# EEG-RM_040218P03.net
KiCad netlist of a schematic drawn in EAGLE
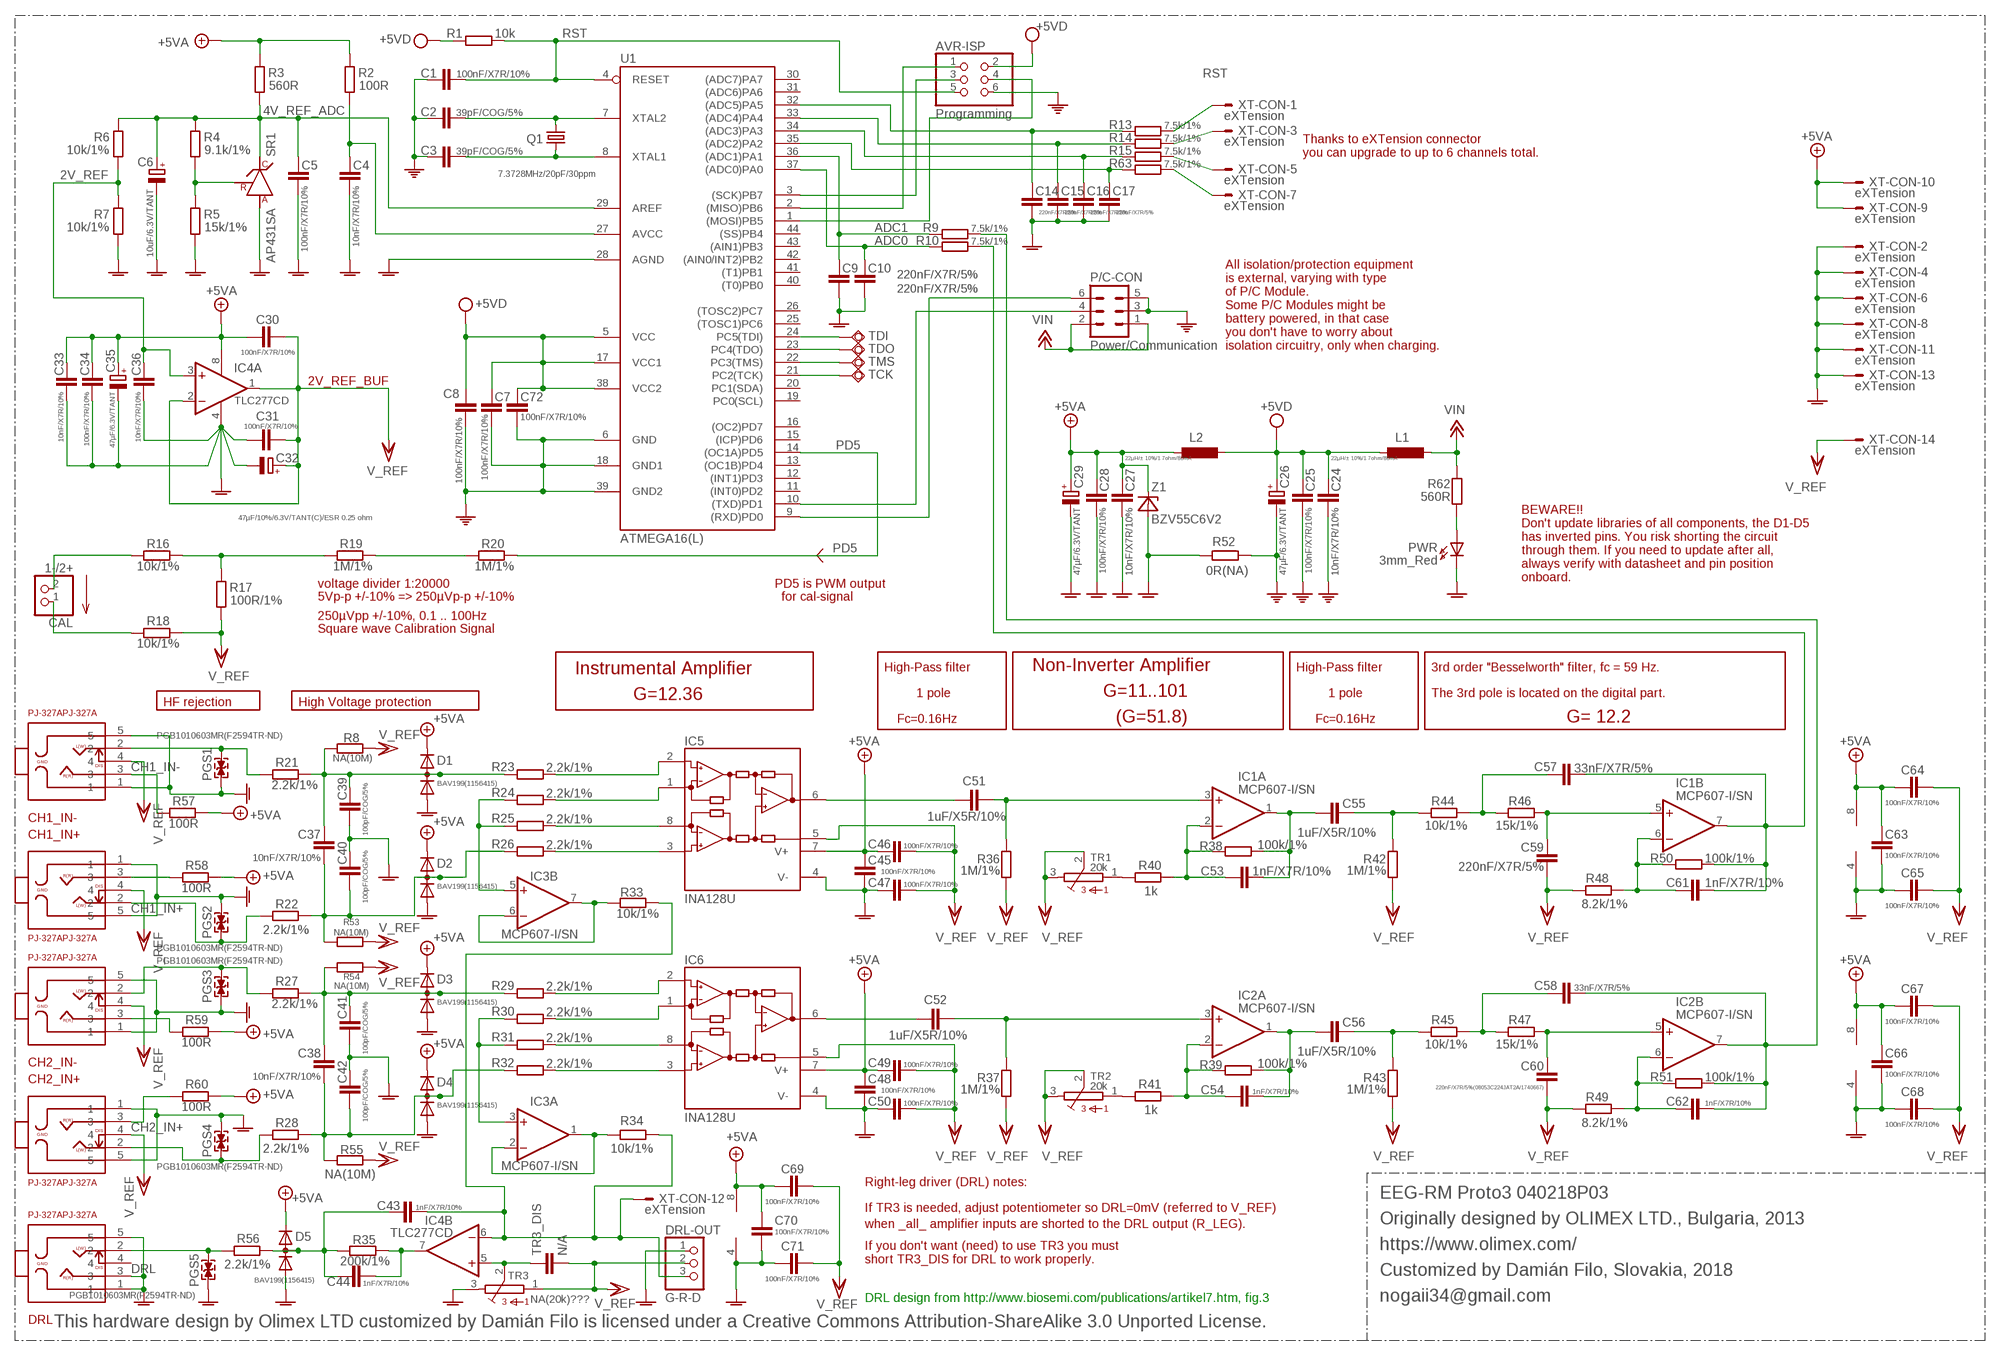
[diagram p0: schematic, sheet 1]

(export (version "E")
  (design (tool "Eeschema 10.0.6"))
  (components
    (comp (ref "AVR-ISP")
      (value "Programming")
      (footprint "eagle-import:2X03")
      (libsource (lib "eagle-import") (part "PINHD-2X3"))
    )
    (comp (ref "C1")
      (value "100nF/X7R/10%")
      (footprint "eagle-import:C0603")
      (libsource (lib "eagle-import") (part "C-EUC0603"))
    )
    (comp (ref "C2")
      (value "39pF/COG/5%")
      (footprint "eagle-import:C0603")
      (libsource (lib "eagle-import") (part "C-EUC0603"))
    )
    (comp (ref "C3")
      (value "39pF/COG/5%")
      (footprint "eagle-import:C0603")
      (libsource (lib "eagle-import") (part "C-EUC0603"))
    )
    (comp (ref "C4")
      (value "10nF/X7R/10%")
      (footprint "eagle-import:C0603")
      (libsource (lib "eagle-import") (part "C-EUC0603"))
    )
    (comp (ref "C5")
      (value "100nF/X7R/10%")
      (footprint "eagle-import:C0603")
      (libsource (lib "eagle-import") (part "C-EUC0603"))
    )
    (comp (ref "C6")
      (value "10uF/6.3V/TANT")
      (footprint "eagle-import:CT3216")
      (libsource (lib "eagle-import") (part "CPOL-EUCT3216"))
    )
    (comp (ref "C7")
      (value "100nF/X7R/10%")
      (footprint "eagle-import:C0603")
      (libsource (lib "eagle-import") (part "C-EUC0603"))
    )
    (comp (ref "C8")
      (value "100nF/X7R/10%")
      (footprint "eagle-import:C0603")
      (libsource (lib "eagle-import") (part "C-EUC0603"))
    )
    (comp (ref "C9")
      (value "220nF/X7R/5%")
      (footprint "eagle-import:C0603")
      (libsource (lib "eagle-import") (part "C-EUC0603"))
    )
    (comp (ref "C10")
      (value "220nF/X7R/5%")
      (footprint "eagle-import:C0603")
      (libsource (lib "eagle-import") (part "C-EUC0603"))
    )
    (comp (ref "C14")
      (value "220nF/X7R/5%")
      (footprint "eagle-import:C0603")
      (libsource (lib "eagle-import") (part "C-EUC0603"))
    )
    (comp (ref "C15")
      (value "220nF/X7R/5%")
      (footprint "eagle-import:C0603")
      (libsource (lib "eagle-import") (part "C-EUC0603"))
    )
    (comp (ref "C16")
      (value "220nF/X7R/5%")
      (footprint "eagle-import:C0603")
      (libsource (lib "eagle-import") (part "C-EUC0603"))
    )
    (comp (ref "C17")
      (value "220nF/X7R/5%")
      (footprint "eagle-import:C0603")
      (libsource (lib "eagle-import") (part "C-EUC0603"))
    )
    (comp (ref "C24")
      (value "10nF/X7R/10%")
      (footprint "eagle-import:C0603")
      (libsource (lib "eagle-import") (part "C-EUC0603"))
    )
    (comp (ref "C25")
      (value "100nF/X7R/10%")
      (footprint "eagle-import:C0603")
      (libsource (lib "eagle-import") (part "C-EUC0603"))
    )
    (comp (ref "C26")
      (value "47µF/6.3V/TANT")
      (footprint "eagle-import:CT3216")
      (libsource (lib "eagle-import") (part "CPOL-EUCT3216"))
    )
    (comp (ref "C27")
      (value "10nF/X7R/10%")
      (footprint "eagle-import:C0603")
      (libsource (lib "eagle-import") (part "C-EUC0603"))
    )
    (comp (ref "C28")
      (value "100nF/X7R/10%")
      (footprint "eagle-import:C0603")
      (libsource (lib "eagle-import") (part "C-EUC0603"))
    )
    (comp (ref "C29")
      (value "47µF/6.3V/TANT")
      (footprint "eagle-import:CT3216")
      (libsource (lib "eagle-import") (part "CPOL-EUCT3216"))
    )
    (comp (ref "C30")
      (value "100nF/X7R/10%")
      (footprint "eagle-import:C0603")
      (libsource (lib "eagle-import") (part "C-EUC0603"))
    )
    (comp (ref "C31")
      (value "100nF/X7R/10%")
      (footprint "eagle-import:C0603")
      (libsource (lib "eagle-import") (part "C-EUC0603"))
    )
    (comp (ref "C32")
      (value "47µF/10%/6.3V/TANT(C)/ESR 0.25 ohm")
      (footprint "eagle-import:CT3528")
      (libsource (lib "eagle-import") (part "CPOL-EUCT3528"))
    )
    (comp (ref "C33")
      (value "10nF/X7R/10%")
      (footprint "eagle-import:C0603")
      (libsource (lib "eagle-import") (part "C-EUC0603"))
    )
    (comp (ref "C34")
      (value "100nF/X7R/10%")
      (footprint "eagle-import:C0603")
      (libsource (lib "eagle-import") (part "C-EUC0603"))
    )
    (comp (ref "C35")
      (value "47µF/6.3V/TANT")
      (footprint "eagle-import:CT3216")
      (libsource (lib "eagle-import") (part "CPOL-EUCT3216"))
    )
    (comp (ref "C36")
      (value "10nF/X7R/10%")
      (footprint "eagle-import:C0603")
      (libsource (lib "eagle-import") (part "C-EUC0603"))
    )
    (comp (ref "C37")
      (value "10nF/X7R/10%")
      (footprint "eagle-import:C0603")
      (libsource (lib "eagle-import") (part "C-EUC0603"))
    )
    (comp (ref "C38")
      (value "10nF/X7R/10%")
      (footprint "eagle-import:C0603")
      (libsource (lib "eagle-import") (part "C-EUC0603"))
    )
    (comp (ref "C39")
      (value "100pF/COG/5%")
      (footprint "eagle-import:C0603")
      (libsource (lib "eagle-import") (part "C-EUC0603"))
    )
    (comp (ref "C40")
      (value "100pF/COG/5%")
      (footprint "eagle-import:C0603")
      (libsource (lib "eagle-import") (part "C-EUC0603"))
    )
    (comp (ref "C41")
      (value "100pF/COG/5%")
      (footprint "eagle-import:C0603")
      (libsource (lib "eagle-import") (part "C-EUC0603"))
    )
    (comp (ref "C42")
      (value "100pF/COG/5%")
      (footprint "eagle-import:C0603")
      (libsource (lib "eagle-import") (part "C-EUC0603"))
    )
    (comp (ref "C43")
      (value "1nF/X7R/10%")
      (footprint "eagle-import:C0603")
      (libsource (lib "eagle-import") (part "C-EUC0603"))
    )
    (comp (ref "C44")
      (value "1nF/X7R/10%")
      (footprint "eagle-import:C0603")
      (libsource (lib "eagle-import") (part "C-EUC0603"))
    )
    (comp (ref "C45")
      (value "100nF/X7R/10%")
      (footprint "eagle-import:C0603")
      (libsource (lib "eagle-import") (part "C-EUC0603"))
    )
    (comp (ref "C46")
      (value "100nF/X7R/10%")
      (footprint "eagle-import:C0603")
      (libsource (lib "eagle-import") (part "C-EUC0603"))
    )
    (comp (ref "C47")
      (value "100nF/X7R/10%")
      (footprint "eagle-import:C0603")
      (libsource (lib "eagle-import") (part "C-EUC0603"))
    )
    (comp (ref "C48")
      (value "100nF/X7R/10%")
      (footprint "eagle-import:C0603")
      (libsource (lib "eagle-import") (part "C-EUC0603"))
    )
    (comp (ref "C49")
      (value "100nF/X7R/10%")
      (footprint "eagle-import:C0603")
      (libsource (lib "eagle-import") (part "C-EUC0603"))
    )
    (comp (ref "C50")
      (value "100nF/X7R/10%")
      (footprint "eagle-import:C0603")
      (libsource (lib "eagle-import") (part "C-EUC0603"))
    )
    (comp (ref "C51")
      (value "1uF/X5R/10%")
      (footprint "eagle-import:C0603")
      (libsource (lib "eagle-import") (part "C-EUC0603"))
    )
    (comp (ref "C52")
      (value "1uF/X5R/10%")
      (footprint "eagle-import:C0603")
      (libsource (lib "eagle-import") (part "C-EUC0603"))
    )
    (comp (ref "C53")
      (value "1nF/X7R/10%")
      (footprint "eagle-import:C0603")
      (libsource (lib "eagle-import") (part "C-EUC0603"))
    )
    (comp (ref "C54")
      (value "1nF/X7R/10%")
      (footprint "eagle-import:C0603")
      (libsource (lib "eagle-import") (part "C-EUC0603"))
    )
    (comp (ref "C55")
      (value "1uF/X5R/10%")
      (footprint "eagle-import:C0603")
      (libsource (lib "eagle-import") (part "C-EUC0603"))
    )
    (comp (ref "C56")
      (value "1uF/X5R/10%")
      (footprint "eagle-import:C0603")
      (libsource (lib "eagle-import") (part "C-EUC0603"))
    )
    (comp (ref "C57")
      (value "33nF/X7R/5%")
      (footprint "eagle-import:C0603")
      (libsource (lib "eagle-import") (part "C-EUC0603"))
    )
    (comp (ref "C58")
      (value "33nF/X7R/5%")
      (footprint "eagle-import:C0603")
      (libsource (lib "eagle-import") (part "C-EUC0603"))
    )
    (comp (ref "C59")
      (value "220nF/X7R/5%")
      (footprint "eagle-import:C0603")
      (libsource (lib "eagle-import") (part "C-EUC0603"))
    )
    (comp (ref "C60")
      (value "220nF/X7R/5%(08053C224JAT2A/1740667)")
      (footprint "eagle-import:C0603")
      (libsource (lib "eagle-import") (part "C-EUC0603"))
    )
    (comp (ref "C61")
      (value "1nF/X7R/10%")
      (footprint "eagle-import:C0603")
      (libsource (lib "eagle-import") (part "C-EUC0603"))
    )
    (comp (ref "C62")
      (value "1nF/X7R/10%")
      (footprint "eagle-import:C0603")
      (libsource (lib "eagle-import") (part "C-EUC0603"))
    )
    (comp (ref "C63")
      (value "100nF/X7R/10%")
      (footprint "eagle-import:C0603")
      (libsource (lib "eagle-import") (part "C-EUC0603"))
    )
    (comp (ref "C64")
      (value "100nF/X7R/10%")
      (footprint "eagle-import:C0603")
      (libsource (lib "eagle-import") (part "C-EUC0603"))
    )
    (comp (ref "C65")
      (value "100nF/X7R/10%")
      (footprint "eagle-import:C0603")
      (libsource (lib "eagle-import") (part "C-EUC0603"))
    )
    (comp (ref "C66")
      (value "100nF/X7R/10%")
      (footprint "eagle-import:C0603")
      (libsource (lib "eagle-import") (part "C-EUC0603"))
    )
    (comp (ref "C67")
      (value "100nF/X7R/10%")
      (footprint "eagle-import:C0603")
      (libsource (lib "eagle-import") (part "C-EUC0603"))
    )
    (comp (ref "C68")
      (value "100nF/X7R/10%")
      (footprint "eagle-import:C0603")
      (libsource (lib "eagle-import") (part "C-EUC0603"))
    )
    (comp (ref "C69")
      (value "100nF/X7R/10%")
      (footprint "eagle-import:C0603")
      (libsource (lib "eagle-import") (part "C-EUC0603"))
    )
    (comp (ref "C70")
      (value "100nF/X7R/10%")
      (footprint "eagle-import:C0603")
      (libsource (lib "eagle-import") (part "C-EUC0603"))
    )
    (comp (ref "C71")
      (value "100nF/X7R/10%")
      (footprint "eagle-import:C0603")
      (libsource (lib "eagle-import") (part "C-EUC0603"))
    )
    (comp (ref "C72")
      (value "100nF/X7R/10%")
      (footprint "eagle-import:C0603")
      (libsource (lib "eagle-import") (part "C-EUC0603"))
    )
    (comp (ref "CAL")
      (value "1-/2+")
      (footprint "eagle-import:1X02")
      (libsource (lib "eagle-import") (part "PINHD-1X2"))
    )
    (comp (ref "CH1_IN+")
      (value "PJ-327APJ-327A")
      (footprint "eagle-import:PJ-327A")
      (libsource (lib "eagle-import") (part "PJ-327APJ-327A"))
    )
    (comp (ref "CH1_IN-")
      (value "PJ-327APJ-327A")
      (footprint "eagle-import:PJ-327A")
      (libsource (lib "eagle-import") (part "PJ-327APJ-327A"))
    )
    (comp (ref "CH2_IN+")
      (value "PJ-327APJ-327A")
      (footprint "eagle-import:PJ-327A")
      (libsource (lib "eagle-import") (part "PJ-327APJ-327A"))
    )
    (comp (ref "CH2_IN-")
      (value "PJ-327APJ-327A")
      (footprint "eagle-import:PJ-327A")
      (libsource (lib "eagle-import") (part "PJ-327APJ-327A"))
    )
    (comp (ref "D1")
      (value "BAV199(1156415)")
      (footprint "eagle-import:SOT23C")
      (libsource (lib "eagle-import") (part "DIODE_AC-AC__"))
    )
    (comp (ref "D2")
      (value "BAV199(1156415)")
      (footprint "eagle-import:SOT23C")
      (libsource (lib "eagle-import") (part "DIODE_AC-AC__"))
    )
    (comp (ref "D3")
      (value "BAV199(1156415)")
      (footprint "eagle-import:SOT23C")
      (libsource (lib "eagle-import") (part "DIODE_AC-AC__"))
    )
    (comp (ref "D4")
      (value "BAV199(1156415)")
      (footprint "eagle-import:SOT23C")
      (libsource (lib "eagle-import") (part "DIODE_AC-AC__"))
    )
    (comp (ref "D5")
      (value "BAV199(1156415)")
      (footprint "eagle-import:SOT23C")
      (libsource (lib "eagle-import") (part "DIODE_AC-AC__"))
    )
    (comp (ref "DRL")
      (value "PJ-327APJ-327A")
      (footprint "eagle-import:PJ-327A")
      (libsource (lib "eagle-import") (part "PJ-327APJ-327A"))
    )
    (comp (ref "DRL-OUT")
      (value "G-R-D")
      (footprint "eagle-import:1X03")
      (libsource (lib "eagle-import") (part "PINHD-1X3"))
    )
    (comp (ref "IC1")
      (value "MCP607-I/SN")
      (footprint "eagle-import:SO08")
      (libsource (lib "eagle-import") (part "LM358D"))
    )
    (comp (ref "IC2")
      (value "MCP607-I/SN")
      (footprint "eagle-import:SO08")
      (libsource (lib "eagle-import") (part "LM358D"))
    )
    (comp (ref "IC3")
      (value "MCP607-I/SN")
      (footprint "eagle-import:SO08")
      (libsource (lib "eagle-import") (part "LM358D"))
    )
    (comp (ref "IC4")
      (value "TLC277CD")
      (footprint "eagle-import:SO08")
      (libsource (lib "eagle-import") (part "LM358D"))
    )
    (comp (ref "IC5")
      (value "INA128U")
      (footprint "eagle-import:SO08")
      (fields (field (name "MF") "TEXAS INSTRUMENTS"))
      (libsource (lib "eagle-import") (part "INA128U"))
    )
    (comp (ref "IC6")
      (value "INA128U")
      (footprint "eagle-import:SO08")
      (fields (field (name "MF") "TEXAS INSTRUMENTS"))
      (libsource (lib "eagle-import") (part "INA128U"))
    )
    (comp (ref "L1")
      (value "22µH/± 10%/1.7ohm/80mA")
      (footprint "eagle-import:L2012C")
      (libsource (lib "eagle-import") (part "L-EUL2012C"))
    )
    (comp (ref "L2")
      (value "22µH/± 10%/1.7ohm/80mA")
      (footprint "eagle-import:L2012C")
      (libsource (lib "eagle-import") (part "L-EUL2012C"))
    )
    (comp (ref "P/C-CON")
      (value "Power/Communication")
      (footprint "eagle-import:ML6L")
      (libsource (lib "eagle-import") (part "ML6L"))
    )
    (comp (ref "PGS1")
      (value "PGB1010603MR(F2594TR-ND)")
      (footprint "eagle-import:0603")
      (libsource (lib "eagle-import") (part "PGB1010603MR(F2594TR-ND)"))
    )
    (comp (ref "PGS2")
      (value "PGB1010603MR(F2594TR-ND)")
      (footprint "eagle-import:0603")
      (libsource (lib "eagle-import") (part "PGB1010603MR(F2594TR-ND)"))
    )
    (comp (ref "PGS3")
      (value "PGB1010603MR(F2594TR-ND)")
      (footprint "eagle-import:0603")
      (libsource (lib "eagle-import") (part "PGB1010603MR(F2594TR-ND)"))
    )
    (comp (ref "PGS4")
      (value "PGB1010603MR(F2594TR-ND)")
      (footprint "eagle-import:0603")
      (libsource (lib "eagle-import") (part "PGB1010603MR(F2594TR-ND)"))
    )
    (comp (ref "PGS5")
      (value "PGB1010603MR(F2594TR-ND)")
      (footprint "eagle-import:0603")
      (libsource (lib "eagle-import") (part "PGB1010603MR(F2594TR-ND)"))
    )
    (comp (ref "PWR")
      (value "3mm_Red")
      (footprint "eagle-import:LED-3.0MM")
      (libsource (lib "eagle-import") (part "LED3.0MM"))
    )
    (comp (ref "Q1")
      (value "7.3728MHz/20pF/30ppm")
      (footprint "eagle-import:HC49_SMD2_THIN")
      (libsource (lib "eagle-import") (part "HC49/S1"))
    )
    (comp (ref "R1")
      (value "10k")
      (footprint "eagle-import:R0603")
      (libsource (lib "eagle-import") (part "R-EU_R0603"))
    )
    (comp (ref "R2")
      (value "100R")
      (footprint "eagle-import:R0603")
      (libsource (lib "eagle-import") (part "R-EU_R0603"))
    )
    (comp (ref "R3")
      (value "560R")
      (footprint "eagle-import:R0603")
      (libsource (lib "eagle-import") (part "R-EU_R0603"))
    )
    (comp (ref "R4")
      (value "9.1k/1%")
      (footprint "eagle-import:R0603")
      (libsource (lib "eagle-import") (part "R-EU_R0603"))
    )
    (comp (ref "R5")
      (value "15k/1%")
      (footprint "eagle-import:R0603")
      (libsource (lib "eagle-import") (part "R-EU_R0603"))
    )
    (comp (ref "R6")
      (value "10k/1%")
      (footprint "eagle-import:R0603")
      (libsource (lib "eagle-import") (part "R-EU_R0603"))
    )
    (comp (ref "R7")
      (value "10k/1%")
      (footprint "eagle-import:R0603")
      (libsource (lib "eagle-import") (part "R-EU_R0603"))
    )
    (comp (ref "R8")
      (value "NA(10M)")
      (footprint "eagle-import:R0603")
      (libsource (lib "eagle-import") (part "R-EU_R0603"))
    )
    (comp (ref "R9")
      (value "7.5k/1%")
      (footprint "eagle-import:M2012")
      (libsource (lib "eagle-import") (part "R-EU_M2012"))
    )
    (comp (ref "R10")
      (value "7.5k/1%")
      (footprint "eagle-import:M2012")
      (libsource (lib "eagle-import") (part "R-EU_M2012"))
    )
    (comp (ref "R13")
      (value "7.5k/1%")
      (footprint "eagle-import:M2012")
      (libsource (lib "eagle-import") (part "R-EU_M2012"))
    )
    (comp (ref "R14")
      (value "7.5k/1%")
      (footprint "eagle-import:M2012")
      (libsource (lib "eagle-import") (part "R-EU_M2012"))
    )
    (comp (ref "R15")
      (value "7.5k/1%")
      (footprint "eagle-import:M2012")
      (libsource (lib "eagle-import") (part "R-EU_M2012"))
    )
    (comp (ref "R16")
      (value "10k/1%")
      (footprint "eagle-import:R0603")
      (libsource (lib "eagle-import") (part "R-EU_R0603"))
    )
    (comp (ref "R17")
      (value "100R/1%")
      (footprint "eagle-import:R0603")
      (libsource (lib "eagle-import") (part "R-EU_R0603"))
    )
    (comp (ref "R18")
      (value "10k/1%")
      (footprint "eagle-import:R0603")
      (libsource (lib "eagle-import") (part "R-EU_R0603"))
    )
    (comp (ref "R19")
      (value "1M/1%")
      (footprint "eagle-import:R0603")
      (libsource (lib "eagle-import") (part "R-EU_R0603"))
    )
    (comp (ref "R20")
      (value "1M/1%")
      (footprint "eagle-import:R0603")
      (libsource (lib "eagle-import") (part "R-EU_R0603"))
    )
    (comp (ref "R21")
      (value "2.2k/1%")
      (footprint "eagle-import:R0603")
      (libsource (lib "eagle-import") (part "R-EU_R0603"))
    )
    (comp (ref "R22")
      (value "2.2k/1%")
      (footprint "eagle-import:R0603")
      (libsource (lib "eagle-import") (part "R-EU_R0603"))
    )
    (comp (ref "R23")
      (value "2.2k/1%")
      (footprint "eagle-import:R0603")
      (libsource (lib "eagle-import") (part "R-EU_R0603"))
    )
    (comp (ref "R24")
      (value "2.2k/1%")
      (footprint "eagle-import:R0603")
      (libsource (lib "eagle-import") (part "R-EU_R0603"))
    )
    (comp (ref "R25")
      (value "2.2k/1%")
      (footprint "eagle-import:R0603")
      (libsource (lib "eagle-import") (part "R-EU_R0603"))
    )
    (comp (ref "R26")
      (value "2.2k/1%")
      (footprint "eagle-import:R0603")
      (libsource (lib "eagle-import") (part "R-EU_R0603"))
    )
    (comp (ref "R27")
      (value "2.2k/1%")
      (footprint "eagle-import:R0603")
      (libsource (lib "eagle-import") (part "R-EU_R0603"))
    )
    (comp (ref "R28")
      (value "2.2k/1%")
      (footprint "eagle-import:R0603")
      (libsource (lib "eagle-import") (part "R-EU_R0603"))
    )
    (comp (ref "R29")
      (value "2.2k/1%")
      (footprint "eagle-import:R0603")
      (libsource (lib "eagle-import") (part "R-EU_R0603"))
    )
    (comp (ref "R30")
      (value "2.2k/1%")
      (footprint "eagle-import:R0603")
      (libsource (lib "eagle-import") (part "R-EU_R0603"))
    )
    (comp (ref "R31")
      (value "2.2k/1%")
      (footprint "eagle-import:R0603")
      (libsource (lib "eagle-import") (part "R-EU_R0603"))
    )
    (comp (ref "R32")
      (value "2.2k/1%")
      (footprint "eagle-import:R0603")
      (libsource (lib "eagle-import") (part "R-EU_R0603"))
    )
    (comp (ref "R33")
      (value "10k/1%")
      (footprint "eagle-import:R0603")
      (libsource (lib "eagle-import") (part "R-EU_R0603"))
    )
    (comp (ref "R34")
      (value "10k/1%")
      (footprint "eagle-import:R0603")
      (libsource (lib "eagle-import") (part "R-EU_R0603"))
    )
    (comp (ref "R35")
      (value "200k/1%")
      (footprint "eagle-import:R0603")
      (libsource (lib "eagle-import") (part "R-EU_R0603"))
    )
    (comp (ref "R36")
      (value "1M/1%")
      (footprint "eagle-import:R0603")
      (libsource (lib "eagle-import") (part "R-EU_R0603"))
    )
    (comp (ref "R37")
      (value "1M/1%")
      (footprint "eagle-import:R0603")
      (libsource (lib "eagle-import") (part "R-EU_R0603"))
    )
    (comp (ref "R38")
      (value "100k/1%")
      (footprint "eagle-import:R0603")
      (libsource (lib "eagle-import") (part "R-EU_R0603"))
    )
    (comp (ref "R39")
      (value "100k/1%")
      (footprint "eagle-import:R0603")
      (libsource (lib "eagle-import") (part "R-EU_R0603"))
    )
    (comp (ref "R40")
      (value "1k")
      (footprint "eagle-import:R0603")
      (libsource (lib "eagle-import") (part "R-EU_R0603"))
    )
    (comp (ref "R41")
      (value "1k")
      (footprint "eagle-import:R0603")
      (libsource (lib "eagle-import") (part "R-EU_R0603"))
    )
    (comp (ref "R42")
      (value "1M/1%")
      (footprint "eagle-import:R0603")
      (libsource (lib "eagle-import") (part "R-EU_R0603"))
    )
    (comp (ref "R43")
      (value "1M/1%")
      (footprint "eagle-import:R0603")
      (libsource (lib "eagle-import") (part "R-EU_R0603"))
    )
    (comp (ref "R44")
      (value "10k/1%")
      (footprint "eagle-import:R0603")
      (libsource (lib "eagle-import") (part "R-EU_R0603"))
    )
    (comp (ref "R45")
      (value "10k/1%")
      (footprint "eagle-import:R0603")
      (libsource (lib "eagle-import") (part "R-EU_R0603"))
    )
    (comp (ref "R46")
      (value "15k/1%")
      (footprint "eagle-import:R0603")
      (libsource (lib "eagle-import") (part "R-EU_R0603"))
    )
    (comp (ref "R47")
      (value "15k/1%")
      (footprint "eagle-import:R0603")
      (libsource (lib "eagle-import") (part "R-EU_R0603"))
    )
    (comp (ref "R48")
      (value "8.2k/1%")
      (footprint "eagle-import:R0603")
      (libsource (lib "eagle-import") (part "R-EU_R0603"))
    )
    (comp (ref "R49")
      (value "8.2k/1%")
      (footprint "eagle-import:R0603")
      (libsource (lib "eagle-import") (part "R-EU_R0603"))
    )
    (comp (ref "R50")
      (value "100k/1%")
      (footprint "eagle-import:R0603")
      (libsource (lib "eagle-import") (part "R-EU_R0603"))
    )
    (comp (ref "R51")
      (value "100k/1%")
      (footprint "eagle-import:R0603")
      (libsource (lib "eagle-import") (part "R-EU_R0603"))
    )
    (comp (ref "R52")
      (value "0R(NA)")
      (footprint "eagle-import:R0603")
      (libsource (lib "eagle-import") (part "R-EU_R0603"))
    )
    (comp (ref "R53")
      (value "NA(10M)")
      (footprint "eagle-import:R0603")
      (libsource (lib "eagle-import") (part "R-EU_R0603"))
    )
    (comp (ref "R54")
      (value "NA(10M)")
      (footprint "eagle-import:R0603")
      (libsource (lib "eagle-import") (part "R-EU_R0603"))
    )
    (comp (ref "R55")
      (value "NA(10M)")
      (footprint "eagle-import:R0603")
      (libsource (lib "eagle-import") (part "R-EU_R0603"))
    )
    (comp (ref "R56")
      (value "2.2k/1%")
      (footprint "eagle-import:R0603")
      (libsource (lib "eagle-import") (part "R-EU_R0603"))
    )
    (comp (ref "R57")
      (value "100R")
      (footprint "eagle-import:R0603")
      (libsource (lib "eagle-import") (part "R-EU_R0603"))
    )
    (comp (ref "R58")
      (value "100R")
      (footprint "eagle-import:R0603")
      (libsource (lib "eagle-import") (part "R-EU_R0603"))
    )
    (comp (ref "R59")
      (value "100R")
      (footprint "eagle-import:R0603")
      (libsource (lib "eagle-import") (part "R-EU_R0603"))
    )
    (comp (ref "R60")
      (value "100R")
      (footprint "eagle-import:R0603")
      (libsource (lib "eagle-import") (part "R-EU_R0603"))
    )
    (comp (ref "R62")
      (value "560R")
      (footprint "eagle-import:R0603")
      (libsource (lib "eagle-import") (part "R-EU_R0603"))
    )
    (comp (ref "R63")
      (value "7.5k/1%")
      (footprint "eagle-import:M2012")
      (libsource (lib "eagle-import") (part "R-EU_M2012"))
    )
    (comp (ref "SR1")
      (value "AP431SA")
      (footprint "eagle-import:SOT-23")
      (libsource (lib "eagle-import") (part "TL431'''"))
    )
    (comp (ref "TCK")
      (value "TESTPAD80/30")
      (footprint "eagle-import:SMD80_30")
      (libsource (lib "eagle-import") (part "TESTPAD80/30"))
    )
    (comp (ref "TDI")
      (value "TESTPAD80/30")
      (footprint "eagle-import:SMD80_30")
      (libsource (lib "eagle-import") (part "TESTPAD80/30"))
    )
    (comp (ref "TDO")
      (value "TESTPAD80/30")
      (footprint "eagle-import:SMD80_30")
      (libsource (lib "eagle-import") (part "TESTPAD80/30"))
    )
    (comp (ref "TMS")
      (value "TESTPAD80/30")
      (footprint "eagle-import:SMD80_30")
      (libsource (lib "eagle-import") (part "TESTPAD80/30"))
    )
    (comp (ref "TR1")
      (value "20k")
      (footprint "eagle-import:S64Y")
      (libsource (lib "eagle-import") (part "S64Y"))
    )
    (comp (ref "TR2")
      (value "20k")
      (footprint "eagle-import:S64Y")
      (libsource (lib "eagle-import") (part "S64Y"))
    )
    (comp (ref "TR3")
      (value "NA(20k)???")
      (footprint "eagle-import:S64Y")
      (libsource (lib "eagle-import") (part "S64Y"))
    )
    (comp (ref "TR3_DIS")
      (value "N/A")
      (footprint "eagle-import:C0402")
      (libsource (lib "eagle-import") (part "C-EUC0402"))
    )
    (comp (ref "U1")
      (value "ATMEGA16(L)")
      (footprint "eagle-import:44TQFP")
      (libsource (lib "eagle-import") (part "ATMEGA16"))
    )
    (comp (ref "XT-CON")
      (value "eXTension")
      (footprint "eagle-import:ML14L")
      (libsource (lib "eagle-import") (part "ML14EL"))
    )
    (comp (ref "Z1")
      (value "BZV55C6V2")
      (footprint "eagle-import:MINI-MELF")
      (libsource (lib "eagle-import") (part "ZDIOD-SMD"))
    )
  )
  (nets
    (net (code "1") (name "+5VA") (class "Default")
      (node (ref "C27") (pin "1") (pinfunction "1_1") (pintype "passive"))
      (node (ref "C28") (pin "1") (pinfunction "1_1") (pintype "passive"))
      (node (ref "C29") (pin "+") (pinfunction "+_+") (pintype "passive"))
      (node (ref "C30") (pin "2") (pinfunction "2_2") (pintype "passive"))
      (node (ref "C33") (pin "1") (pinfunction "1_1") (pintype "passive"))
      (node (ref "C34") (pin "1") (pinfunction "1_1") (pintype "passive"))
      (node (ref "C35") (pin "+") (pinfunction "+_+") (pintype "passive"))
      (node (ref "C45") (pin "1") (pinfunction "1_1") (pintype "passive"))
      (node (ref "C46") (pin "1") (pinfunction "1_1") (pintype "passive"))
      (node (ref "C48") (pin "1") (pinfunction "1_1") (pintype "passive"))
      (node (ref "C49") (pin "1") (pinfunction "1_1") (pintype "passive"))
      (node (ref "C63") (pin "1") (pinfunction "1_1") (pintype "passive"))
      (node (ref "C64") (pin "1") (pinfunction "1_1") (pintype "passive"))
      (node (ref "C66") (pin "1") (pinfunction "1_1") (pintype "passive"))
      (node (ref "C67") (pin "1") (pinfunction "1_1") (pintype "passive"))
      (node (ref "C69") (pin "1") (pinfunction "1_1") (pintype "passive"))
      (node (ref "C70") (pin "1") (pinfunction "1_1") (pintype "passive"))
      (node (ref "D1") (pin "1") (pinfunction "K_1") (pintype "passive"))
      (node (ref "D2") (pin "1") (pinfunction "K_1") (pintype "passive"))
      (node (ref "D3") (pin "1") (pinfunction "K_1") (pintype "passive"))
      (node (ref "D4") (pin "1") (pinfunction "K_1") (pintype "passive"))
      (node (ref "D5") (pin "1") (pinfunction "K_1") (pintype "passive"))
      (node (ref "IC1") (pin "8") (pinfunction "V+_8") (pintype "power_in"))
      (node (ref "IC2") (pin "8") (pinfunction "V+_8") (pintype "power_in"))
      (node (ref "IC3") (pin "8") (pinfunction "V+_8") (pintype "power_in"))
      (node (ref "IC4") (pin "8") (pinfunction "V+_8") (pintype "power_in"))
      (node (ref "IC5") (pin "7") (pinfunction "V+_7") (pintype "power_in"))
      (node (ref "IC6") (pin "7") (pinfunction "V+_7") (pintype "power_in"))
      (node (ref "L2") (pin "2") (pinfunction "2_2") (pintype "passive"))
      (node (ref "R2") (pin "2") (pinfunction "2_2") (pintype "passive"))
      (node (ref "R3") (pin "2") (pinfunction "2_2") (pintype "passive"))
      (node (ref "R57") (pin "2") (pinfunction "2_2") (pintype "passive"))
      (node (ref "R58") (pin "2") (pinfunction "2_2") (pintype "passive"))
      (node (ref "R59") (pin "2") (pinfunction "2_2") (pintype "passive"))
      (node (ref "R60") (pin "2") (pinfunction "2_2") (pintype "passive"))
      (node (ref "XT-CON") (pin "10") (pinfunction "S_10") (pintype "passive"))
      (node (ref "XT-CON") (pin "9") (pinfunction "S_9") (pintype "passive"))
      (node (ref "Z1") (pin "1") (pinfunction "C_1") (pintype "passive"))
    )
    (net (code "2") (name "+5VD") (class "Default")
      (node (ref "AVR-ISP") (pin "2") (pinfunction "2_2") (pintype "passive"))
      (node (ref "C24") (pin "1") (pinfunction "1_1") (pintype "passive"))
      (node (ref "C25") (pin "1") (pinfunction "1_1") (pintype "passive"))
      (node (ref "C26") (pin "+") (pinfunction "+_+") (pintype "passive"))
      (node (ref "C7") (pin "1") (pinfunction "1_1") (pintype "passive"))
      (node (ref "C72") (pin "1") (pinfunction "1_1") (pintype "passive"))
      (node (ref "C8") (pin "1") (pinfunction "1_1") (pintype "passive"))
      (node (ref "L1") (pin "2") (pinfunction "2_2") (pintype "passive"))
      (node (ref "L2") (pin "1") (pinfunction "1_1") (pintype "passive"))
      (node (ref "R1") (pin "1") (pinfunction "1_1") (pintype "passive"))
      (node (ref "U1") (pin "17") (pinfunction "VCC1_17") (pintype "bidirectional"))
      (node (ref "U1") (pin "38") (pinfunction "VCC2_38") (pintype "bidirectional"))
      (node (ref "U1") (pin "5") (pinfunction "VCC_5") (pintype "power_in"))
    )
    (net (code "3") (name "/2V_REF") (class "Default")
      (node (ref "C36") (pin "1") (pinfunction "1_1") (pintype "passive"))
      (node (ref "IC4") (pin "3") (pinfunction "+IN_3") (pintype "input"))
      (node (ref "R6") (pin "1") (pinfunction "1_1") (pintype "passive"))
      (node (ref "R7") (pin "2") (pinfunction "2_2") (pintype "passive"))
    )
    (net (code "4") (name "/4V_REF_ADC") (class "Default")
      (node (ref "C5") (pin "1") (pinfunction "1_1") (pintype "passive"))
      (node (ref "C6") (pin "+") (pinfunction "+_+") (pintype "passive"))
      (node (ref "R3") (pin "1") (pinfunction "1_1") (pintype "passive"))
      (node (ref "R4") (pin "2") (pinfunction "2_2") (pintype "passive"))
      (node (ref "R6") (pin "2") (pinfunction "2_2") (pintype "passive"))
      (node (ref "SR1") (pin "1") (pinfunction "C_1") (pintype "input"))
      (node (ref "U1") (pin "29") (pinfunction "AREF_29") (pintype "power_in"))
    )
    (net (code "5") (name "/ADC0") (class "Default")
      (node (ref "C10") (pin "1") (pinfunction "1_1") (pintype "passive"))
      (node (ref "R10") (pin "1") (pinfunction "1_1") (pintype "passive"))
      (node (ref "U1") (pin "37") (pinfunction "(ADC0)PA0_37") (pintype "bidirectional"))
    )
    (net (code "6") (name "/ADC1") (class "Default")
      (node (ref "C9") (pin "1") (pinfunction "1_1") (pintype "passive"))
      (node (ref "R9") (pin "1") (pinfunction "1_1") (pintype "passive"))
      (node (ref "U1") (pin "36") (pinfunction "(ADC1)PA1_36") (pintype "bidirectional"))
    )
    (net (code "7") (name "/CH1_IN+") (class "Default")
      (node (ref "CH1_IN+") (pin "2") (pinfunction "2_2") (pintype "bidirectional"))
      (node (ref "PGS2") (pin "1") (pinfunction "1_1") (pintype "input"))
      (node (ref "R22") (pin "1") (pinfunction "1_1") (pintype "passive"))
    )
    (net (code "8") (name "/CH1_IN-") (class "Default")
      (node (ref "CH1_IN-") (pin "2") (pinfunction "2_2") (pintype "bidirectional"))
      (node (ref "PGS1") (pin "2") (pinfunction "2_2") (pintype "input"))
      (node (ref "R21") (pin "1") (pinfunction "1_1") (pintype "passive"))
    )
    (net (code "9") (name "/CH2_IN+") (class "Default")
      (node (ref "CH2_IN+") (pin "2") (pinfunction "2_2") (pintype "bidirectional"))
      (node (ref "PGS4") (pin "1") (pinfunction "1_1") (pintype "input"))
      (node (ref "R28") (pin "1") (pinfunction "1_1") (pintype "passive"))
    )
    (net (code "10") (name "/DRL") (class "Default")
      (node (ref "DRL") (pin "2") (pinfunction "2_2") (pintype "bidirectional"))
      (node (ref "PGS5") (pin "2") (pinfunction "2_2") (pintype "input"))
      (node (ref "R56") (pin "1") (pinfunction "1_1") (pintype "passive"))
    )
    (net (code "11") (name "/PD5") (class "Default")
      (node (ref "R20") (pin "2") (pinfunction "2_2") (pintype "passive"))
      (node (ref "U1") (pin "14") (pinfunction "(OC1A)PD5_14") (pintype "bidirectional"))
    )
    (net (code "12") (name "/RST") (class "Default")
      (node (ref "AVR-ISP") (pin "5") (pinfunction "5_5") (pintype "passive"))
      (node (ref "C1") (pin "1") (pinfunction "1_1") (pintype "passive"))
      (node (ref "R1") (pin "2") (pinfunction "2_2") (pintype "passive"))
      (node (ref "U1") (pin "4") (pinfunction "RESET_4") (pintype "input"))
    )
    (net (code "13") (name "GNDA") (class "Default")
      (node (ref "C10") (pin "2") (pinfunction "2_2") (pintype "passive"))
      (node (ref "C14") (pin "2") (pinfunction "2_2") (pintype "passive"))
      (node (ref "C15") (pin "2") (pinfunction "2_2") (pintype "passive"))
      (node (ref "C16") (pin "2") (pinfunction "2_2") (pintype "passive"))
      (node (ref "C17") (pin "2") (pinfunction "2_2") (pintype "passive"))
      (node (ref "C27") (pin "2") (pinfunction "2_2") (pintype "passive"))
      (node (ref "C28") (pin "2") (pinfunction "2_2") (pintype "passive"))
      (node (ref "C29") (pin "-") (pinfunction "-_-") (pintype "passive"))
      (node (ref "C31") (pin "2") (pinfunction "2_2") (pintype "passive"))
      (node (ref "C32") (pin "-") (pinfunction "-_-") (pintype "passive"))
      (node (ref "C33") (pin "2") (pinfunction "2_2") (pintype "passive"))
      (node (ref "C34") (pin "2") (pinfunction "2_2") (pintype "passive"))
      (node (ref "C35") (pin "-") (pinfunction "-_-") (pintype "passive"))
      (node (ref "C36") (pin "2") (pinfunction "2_2") (pintype "passive"))
      (node (ref "C39") (pin "1") (pinfunction "1_1") (pintype "passive"))
      (node (ref "C4") (pin "2") (pinfunction "2_2") (pintype "passive"))
      (node (ref "C40") (pin "2") (pinfunction "2_2") (pintype "passive"))
      (node (ref "C41") (pin "1") (pinfunction "1_1") (pintype "passive"))
      (node (ref "C42") (pin "2") (pinfunction "2_2") (pintype "passive"))
      (node (ref "C45") (pin "2") (pinfunction "2_2") (pintype "passive"))
      (node (ref "C47") (pin "1") (pinfunction "1_1") (pintype "passive"))
      (node (ref "C48") (pin "2") (pinfunction "2_2") (pintype "passive"))
      (node (ref "C5") (pin "2") (pinfunction "2_2") (pintype "passive"))
      (node (ref "C50") (pin "1") (pinfunction "1_1") (pintype "passive"))
      (node (ref "C6") (pin "-") (pinfunction "-_-") (pintype "passive"))
      (node (ref "C63") (pin "2") (pinfunction "2_2") (pintype "passive"))
      (node (ref "C65") (pin "1") (pinfunction "1_1") (pintype "passive"))
      (node (ref "C66") (pin "2") (pinfunction "2_2") (pintype "passive"))
      (node (ref "C68") (pin "1") (pinfunction "1_1") (pintype "passive"))
      (node (ref "C70") (pin "2") (pinfunction "2_2") (pintype "passive"))
      (node (ref "C71") (pin "1") (pinfunction "1_1") (pintype "passive"))
      (node (ref "C9") (pin "2") (pinfunction "2_2") (pintype "passive"))
      (node (ref "CH1_IN+") (pin "1") (pinfunction "1_1") (pintype "bidirectional"))
      (node (ref "CH1_IN+") (pin "5") (pinfunction "5_5") (pintype "bidirectional"))
      (node (ref "CH1_IN-") (pin "1") (pinfunction "1_1") (pintype "bidirectional"))
      (node (ref "CH1_IN-") (pin "5") (pinfunction "5_5") (pintype "bidirectional"))
      (node (ref "CH2_IN+") (pin "1") (pinfunction "1_1") (pintype "bidirectional"))
      (node (ref "CH2_IN+") (pin "5") (pinfunction "5_5") (pintype "bidirectional"))
      (node (ref "CH2_IN-") (pin "1") (pinfunction "1_1") (pintype "bidirectional"))
      (node (ref "CH2_IN-") (pin "5") (pinfunction "5_5") (pintype "bidirectional"))
      (node (ref "D1") (pin "2") (pinfunction "A_2") (pintype "passive"))
      (node (ref "D2") (pin "2") (pinfunction "A_2") (pintype "passive"))
      (node (ref "D3") (pin "2") (pinfunction "A_2") (pintype "passive"))
      (node (ref "D4") (pin "2") (pinfunction "A_2") (pintype "passive"))
      (node (ref "D5") (pin "2") (pinfunction "A_2") (pintype "passive"))
      (node (ref "DRL") (pin "1") (pinfunction "1_1") (pintype "bidirectional"))
      (node (ref "DRL") (pin "3") (pinfunction "3_3") (pintype "bidirectional"))
      (node (ref "DRL") (pin "5") (pinfunction "5_5") (pintype "bidirectional"))
      (node (ref "DRL-OUT") (pin "1") (pinfunction "1_1") (pintype "passive"))
      (node (ref "IC1") (pin "4") (pinfunction "V-_4") (pintype "power_in"))
      (node (ref "IC2") (pin "4") (pinfunction "V-_4") (pintype "power_in"))
      (node (ref "IC3") (pin "4") (pinfunction "V-_4") (pintype "power_in"))
      (node (ref "IC4") (pin "4") (pinfunction "V-_4") (pintype "power_in"))
      (node (ref "IC5") (pin "4") (pinfunction "V-_4") (pintype "power_in"))
      (node (ref "IC6") (pin "4") (pinfunction "V-_4") (pintype "power_in"))
      (node (ref "PGS1") (pin "1") (pinfunction "1_1") (pintype "input"))
      (node (ref "PGS2") (pin "2") (pinfunction "2_2") (pintype "input"))
      (node (ref "PGS3") (pin "1") (pinfunction "1_1") (pintype "input"))
      (node (ref "PGS4") (pin "2") (pinfunction "2_2") (pintype "input"))
      (node (ref "PGS5") (pin "1") (pinfunction "1_1") (pintype "input"))
      (node (ref "PWR") (pin "K") (pinfunction "C_K") (pintype "passive"))
      (node (ref "R5") (pin "1") (pinfunction "1_1") (pintype "passive"))
      (node (ref "R52") (pin "1") (pinfunction "1_1") (pintype "passive"))
      (node (ref "R7") (pin "1") (pinfunction "1_1") (pintype "passive"))
      (node (ref "SR1") (pin "3") (pinfunction "A_3") (pintype "input"))
      (node (ref "TR3") (pin "3") (pinfunction "3_3") (pintype "passive"))
      (node (ref "U1") (pin "28") (pinfunction "AGND_28") (pintype "power_in"))
      (node (ref "XT-CON") (pin "11") (pinfunction "S_11") (pintype "passive"))
      (node (ref "XT-CON") (pin "13") (pinfunction "S_13") (pintype "passive"))
      (node (ref "XT-CON") (pin "2") (pinfunction "S_2") (pintype "passive"))
      (node (ref "XT-CON") (pin "4") (pinfunction "S_4") (pintype "passive"))
      (node (ref "XT-CON") (pin "6") (pinfunction "S_6") (pintype "passive"))
      (node (ref "XT-CON") (pin "8") (pinfunction "S_8") (pintype "passive"))
      (node (ref "Z1") (pin "2") (pinfunction "A_2") (pintype "passive"))
    )
    (net (code "14") (name "Net-(C55-Pad2)") (class "Default")
      (node (ref "C55") (pin "2") (pinfunction "2_2") (pintype "passive"))
      (node (ref "R42") (pin "1") (pinfunction "1_1") (pintype "passive"))
      (node (ref "R44") (pin "1") (pinfunction "1_1") (pintype "passive"))
    )
    (net (code "15") (name "Net-(C56-Pad2)") (class "Default")
      (node (ref "C56") (pin "2") (pinfunction "2_2") (pintype "passive"))
      (node (ref "R43") (pin "1") (pinfunction "1_1") (pintype "passive"))
      (node (ref "R45") (pin "1") (pinfunction "1_1") (pintype "passive"))
    )
    (net (code "16") (name "Net-(C57-Pad1)") (class "Default")
      (node (ref "C57") (pin "1") (pinfunction "1_1") (pintype "passive"))
      (node (ref "R44") (pin "2") (pinfunction "2_2") (pintype "passive"))
      (node (ref "R46") (pin "1") (pinfunction "1_1") (pintype "passive"))
    )
    (net (code "17") (name "Net-(C58-Pad1)") (class "Default")
      (node (ref "C58") (pin "1") (pinfunction "1_1") (pintype "passive"))
      (node (ref "R45") (pin "2") (pinfunction "2_2") (pintype "passive"))
      (node (ref "R47") (pin "1") (pinfunction "1_1") (pintype "passive"))
    )
    (net (code "18") (name "Net-(CAL-Pad1)") (class "Default")
      (node (ref "CAL") (pin "1") (pinfunction "1_1") (pintype "passive"))
      (node (ref "R18") (pin "1") (pinfunction "1_1") (pintype "passive"))
    )
    (net (code "19") (name "Net-(CAL-Pad2)") (class "Default")
      (node (ref "CAL") (pin "2") (pinfunction "2_2") (pintype "passive"))
      (node (ref "R16") (pin "1") (pinfunction "1_1") (pintype "passive"))
    )
    (net (code "20") (name "Net-(CH1_IN+-Pad3)") (class "Default")
      (node (ref "CH1_IN+") (pin "3") (pinfunction "3_3") (pintype "bidirectional"))
      (node (ref "R58") (pin "1") (pinfunction "1_1") (pintype "passive"))
    )
    (net (code "21") (name "Net-(CH1_IN--Pad3)") (class "Default")
      (node (ref "CH1_IN-") (pin "3") (pinfunction "3_3") (pintype "bidirectional"))
      (node (ref "R57") (pin "1") (pinfunction "1_1") (pintype "passive"))
    )
    (net (code "22") (name "Net-(CH2_IN+-Pad3)") (class "Default")
      (node (ref "CH2_IN+") (pin "3") (pinfunction "3_3") (pintype "bidirectional"))
      (node (ref "R60") (pin "1") (pinfunction "1_1") (pintype "passive"))
    )
    (net (code "23") (name "Net-(CH2_IN--Pad2)") (class "Default")
      (node (ref "CH2_IN-") (pin "2") (pinfunction "2_2") (pintype "bidirectional"))
      (node (ref "PGS3") (pin "2") (pinfunction "2_2") (pintype "input"))
      (node (ref "R27") (pin "1") (pinfunction "1_1") (pintype "passive"))
    )
    (net (code "24") (name "Net-(CH2_IN--Pad3)") (class "Default")
      (node (ref "CH2_IN-") (pin "3") (pinfunction "3_3") (pintype "bidirectional"))
      (node (ref "R59") (pin "1") (pinfunction "1_1") (pintype "passive"))
    )
    (net (code "25") (name "Net-(D1-AK)") (class "Default")
      (node (ref "C37") (pin "2") (pinfunction "2_2") (pintype "passive"))
      (node (ref "C39") (pin "2") (pinfunction "2_2") (pintype "passive"))
      (node (ref "D1") (pin "3") (pinfunction "AK_3") (pintype "passive"))
      (node (ref "R21") (pin "2") (pinfunction "2_2") (pintype "passive"))
      (node (ref "R23") (pin "2") (pinfunction "2_2") (pintype "passive"))
      (node (ref "R8") (pin "2") (pinfunction "2_2") (pintype "passive"))
    )
    (net (code "26") (name "Net-(D2-AK)") (class "Default")
      (node (ref "C37") (pin "1") (pinfunction "1_1") (pintype "passive"))
      (node (ref "C40") (pin "1") (pinfunction "1_1") (pintype "passive"))
      (node (ref "D2") (pin "3") (pinfunction "AK_3") (pintype "passive"))
      (node (ref "R22") (pin "2") (pinfunction "2_2") (pintype "passive"))
      (node (ref "R26") (pin "2") (pinfunction "2_2") (pintype "passive"))
      (node (ref "R53") (pin "2") (pinfunction "2_2") (pintype "passive"))
    )
    (net (code "27") (name "Net-(D3-AK)") (class "Default")
      (node (ref "C38") (pin "2") (pinfunction "2_2") (pintype "passive"))
      (node (ref "C41") (pin "2") (pinfunction "2_2") (pintype "passive"))
      (node (ref "D3") (pin "3") (pinfunction "AK_3") (pintype "passive"))
      (node (ref "R27") (pin "2") (pinfunction "2_2") (pintype "passive"))
      (node (ref "R29") (pin "2") (pinfunction "2_2") (pintype "passive"))
      (node (ref "R54") (pin "2") (pinfunction "2_2") (pintype "passive"))
    )
    (net (code "28") (name "Net-(D4-AK)") (class "Default")
      (node (ref "C38") (pin "1") (pinfunction "1_1") (pintype "passive"))
      (node (ref "C42") (pin "1") (pinfunction "1_1") (pintype "passive"))
      (node (ref "D4") (pin "3") (pinfunction "AK_3") (pintype "passive"))
      (node (ref "R28") (pin "2") (pinfunction "2_2") (pintype "passive"))
      (node (ref "R32") (pin "2") (pinfunction "2_2") (pintype "passive"))
      (node (ref "R55") (pin "2") (pinfunction "2_2") (pintype "passive"))
    )
    (net (code "29") (name "Net-(D5-AK)") (class "Default")
      (node (ref "C43") (pin "2") (pinfunction "2_2") (pintype "passive"))
      (node (ref "C44") (pin "2") (pinfunction "2_2") (pintype "passive"))
      (node (ref "D5") (pin "3") (pinfunction "AK_3") (pintype "passive"))
      (node (ref "R35") (pin "1") (pinfunction "1_1") (pintype "passive"))
      (node (ref "R56") (pin "2") (pinfunction "2_2") (pintype "passive"))
    )
    (net (code "30") (name "Net-(IC1A-+IN)") (class "Default")
      (node (ref "C51") (pin "2") (pinfunction "2_2") (pintype "passive"))
      (node (ref "IC1") (pin "3") (pinfunction "+IN_3") (pintype "input"))
      (node (ref "R36") (pin "1") (pinfunction "1_1") (pintype "passive"))
    )
    (net (code "31") (name "Net-(IC1A--IN)") (class "Default")
      (node (ref "C53") (pin "1") (pinfunction "1_1") (pintype "passive"))
      (node (ref "IC1") (pin "2") (pinfunction "-IN_2") (pintype "input"))
      (node (ref "R38") (pin "1") (pinfunction "1_1") (pintype "passive"))
      (node (ref "R40") (pin "1") (pinfunction "1_1") (pintype "passive"))
    )
    (net (code "32") (name "Net-(IC1A-OUT)") (class "Default")
      (node (ref "C53") (pin "2") (pinfunction "2_2") (pintype "passive"))
      (node (ref "C55") (pin "1") (pinfunction "1_1") (pintype "passive"))
      (node (ref "IC1") (pin "1") (pinfunction "OUT_1") (pintype "output"))
      (node (ref "R38") (pin "2") (pinfunction "2_2") (pintype "passive"))
    )
    (net (code "33") (name "Net-(IC1B-+IN)") (class "Default")
      (node (ref "C59") (pin "1") (pinfunction "1_1") (pintype "passive"))
      (node (ref "IC1") (pin "5") (pinfunction "+IN_5") (pintype "input"))
      (node (ref "R46") (pin "2") (pinfunction "2_2") (pintype "passive"))
    )
    (net (code "34") (name "Net-(IC1B--IN)") (class "Default")
      (node (ref "C61") (pin "1") (pinfunction "1_1") (pintype "passive"))
      (node (ref "IC1") (pin "6") (pinfunction "-IN_6") (pintype "input"))
      (node (ref "R48") (pin "1") (pinfunction "1_1") (pintype "passive"))
      (node (ref "R50") (pin "1") (pinfunction "1_1") (pintype "passive"))
    )
    (net (code "35") (name "Net-(IC1B-OUT)") (class "Default")
      (node (ref "C57") (pin "2") (pinfunction "2_2") (pintype "passive"))
      (node (ref "C61") (pin "2") (pinfunction "2_2") (pintype "passive"))
      (node (ref "IC1") (pin "7") (pinfunction "OUT_7") (pintype "output"))
      (node (ref "R10") (pin "2") (pinfunction "2_2") (pintype "passive"))
      (node (ref "R50") (pin "2") (pinfunction "2_2") (pintype "passive"))
    )
    (net (code "36") (name "Net-(IC2A-+IN)") (class "Default")
      (node (ref "C52") (pin "2") (pinfunction "2_2") (pintype "passive"))
      (node (ref "IC2") (pin "3") (pinfunction "+IN_3") (pintype "input"))
      (node (ref "R37") (pin "1") (pinfunction "1_1") (pintype "passive"))
    )
    (net (code "37") (name "Net-(IC2A--IN)") (class "Default")
      (node (ref "C54") (pin "1") (pinfunction "1_1") (pintype "passive"))
      (node (ref "IC2") (pin "2") (pinfunction "-IN_2") (pintype "input"))
      (node (ref "R39") (pin "1") (pinfunction "1_1") (pintype "passive"))
      (node (ref "R41") (pin "1") (pinfunction "1_1") (pintype "passive"))
    )
    (net (code "38") (name "Net-(IC2A-OUT)") (class "Default")
      (node (ref "C54") (pin "2") (pinfunction "2_2") (pintype "passive"))
      (node (ref "C56") (pin "1") (pinfunction "1_1") (pintype "passive"))
      (node (ref "IC2") (pin "1") (pinfunction "OUT_1") (pintype "output"))
      (node (ref "R39") (pin "2") (pinfunction "2_2") (pintype "passive"))
    )
    (net (code "39") (name "Net-(IC2B-+IN)") (class "Default")
      (node (ref "C60") (pin "1") (pinfunction "1_1") (pintype "passive"))
      (node (ref "IC2") (pin "5") (pinfunction "+IN_5") (pintype "input"))
      (node (ref "R47") (pin "2") (pinfunction "2_2") (pintype "passive"))
    )
    (net (code "40") (name "Net-(IC2B--IN)") (class "Default")
      (node (ref "C62") (pin "1") (pinfunction "1_1") (pintype "passive"))
      (node (ref "IC2") (pin "6") (pinfunction "-IN_6") (pintype "input"))
      (node (ref "R49") (pin "1") (pinfunction "1_1") (pintype "passive"))
      (node (ref "R51") (pin "1") (pinfunction "1_1") (pintype "passive"))
    )
    (net (code "41") (name "Net-(IC2B-OUT)") (class "Default")
      (node (ref "C58") (pin "2") (pinfunction "2_2") (pintype "passive"))
      (node (ref "C62") (pin "2") (pinfunction "2_2") (pintype "passive"))
      (node (ref "IC2") (pin "7") (pinfunction "OUT_7") (pintype "output"))
      (node (ref "R51") (pin "2") (pinfunction "2_2") (pintype "passive"))
      (node (ref "R9") (pin "2") (pinfunction "2_2") (pintype "passive"))
    )
    (net (code "42") (name "Net-(IC3A-+IN)") (class "Default")
      (node (ref "IC3") (pin "3") (pinfunction "+IN_3") (pintype "input"))
      (node (ref "R30") (pin "2") (pinfunction "2_2") (pintype "passive"))
      (node (ref "R31") (pin "2") (pinfunction "2_2") (pintype "passive"))
    )
    (net (code "43") (name "Net-(IC3A--IN)") (class "Default")
      (node (ref "IC3") (pin "1") (pinfunction "OUT_1") (pintype "output"))
      (node (ref "IC3") (pin "2") (pinfunction "-IN_2") (pintype "input"))
      (node (ref "R34") (pin "2") (pinfunction "2_2") (pintype "passive"))
    )
    (net (code "44") (name "Net-(IC3B-+IN)") (class "Default")
      (node (ref "IC3") (pin "5") (pinfunction "+IN_5") (pintype "input"))
      (node (ref "R24") (pin "2") (pinfunction "2_2") (pintype "passive"))
      (node (ref "R25") (pin "2") (pinfunction "2_2") (pintype "passive"))
    )
    (net (code "45") (name "Net-(IC3B--IN)") (class "Default")
      (node (ref "IC3") (pin "6") (pinfunction "-IN_6") (pintype "input"))
      (node (ref "IC3") (pin "7") (pinfunction "OUT_7") (pintype "output"))
      (node (ref "R33") (pin "2") (pinfunction "2_2") (pintype "passive"))
    )
    (net (code "46") (name "Net-(IC4B-+IN)") (class "Default")
      (node (ref "IC4") (pin "5") (pinfunction "+IN_5") (pintype "input"))
      (node (ref "TR3") (pin "2") (pinfunction "2_2") (pintype "passive"))
      (node (ref "TR3_DIS") (pin "1") (pinfunction "1_1") (pintype "passive"))
    )
    (net (code "47") (name "Net-(IC4B--IN)") (class "Default")
      (node (ref "C43") (pin "1") (pinfunction "1_1") (pintype "passive"))
      (node (ref "DRL-OUT") (pin "3") (pinfunction "3_3") (pintype "passive"))
      (node (ref "IC4") (pin "6") (pinfunction "-IN_6") (pintype "input"))
      (node (ref "R33") (pin "1") (pinfunction "1_1") (pintype "passive"))
      (node (ref "R34") (pin "1") (pinfunction "1_1") (pintype "passive"))
      (node (ref "XT-CON") (pin "12") (pinfunction "S_12") (pintype "passive"))
    )
    (net (code "48") (name "Net-(IC4B-OUT)") (class "Default")
      (node (ref "C44") (pin "1") (pinfunction "1_1") (pintype "passive"))
      (node (ref "IC4") (pin "7") (pinfunction "OUT_7") (pintype "output"))
      (node (ref "R35") (pin "2") (pinfunction "2_2") (pintype "passive"))
    )
    (net (code "49") (name "Net-(IC5-+IN)") (class "Default")
      (node (ref "IC5") (pin "3") (pinfunction "+IN_3") (pintype "input"))
      (node (ref "R26") (pin "1") (pinfunction "1_1") (pintype "passive"))
    )
    (net (code "50") (name "Net-(IC5--IN)") (class "Default")
      (node (ref "IC5") (pin "2") (pinfunction "-IN_2") (pintype "input"))
      (node (ref "R23") (pin "1") (pinfunction "1_1") (pintype "passive"))
    )
    (net (code "51") (name "Net-(IC5-OUT)") (class "Default")
      (node (ref "C51") (pin "1") (pinfunction "1_1") (pintype "passive"))
      (node (ref "IC5") (pin "6") (pinfunction "OUT_6") (pintype "output"))
    )
    (net (code "52") (name "Net-(IC5-RG-Pad1)") (class "Default")
      (node (ref "IC5") (pin "1") (pinfunction "RG_1") (pintype "passive"))
      (node (ref "R24") (pin "1") (pinfunction "1_1") (pintype "passive"))
    )
    (net (code "53") (name "Net-(IC5-RG-Pad8)") (class "Default")
      (node (ref "IC5") (pin "8") (pinfunction "RG_8") (pintype "passive"))
      (node (ref "R25") (pin "1") (pinfunction "1_1") (pintype "passive"))
    )
    (net (code "54") (name "Net-(IC6-+IN)") (class "Default")
      (node (ref "IC6") (pin "3") (pinfunction "+IN_3") (pintype "input"))
      (node (ref "R32") (pin "1") (pinfunction "1_1") (pintype "passive"))
    )
    (net (code "55") (name "Net-(IC6--IN)") (class "Default")
      (node (ref "IC6") (pin "2") (pinfunction "-IN_2") (pintype "input"))
      (node (ref "R29") (pin "1") (pinfunction "1_1") (pintype "passive"))
    )
    (net (code "56") (name "Net-(IC6-OUT)") (class "Default")
      (node (ref "C52") (pin "1") (pinfunction "1_1") (pintype "passive"))
      (node (ref "IC6") (pin "6") (pinfunction "OUT_6") (pintype "output"))
    )
    (net (code "57") (name "Net-(IC6-RG-Pad1)") (class "Default")
      (node (ref "IC6") (pin "1") (pinfunction "RG_1") (pintype "passive"))
      (node (ref "R30") (pin "1") (pinfunction "1_1") (pintype "passive"))
    )
    (net (code "58") (name "Net-(IC6-RG-Pad8)") (class "Default")
      (node (ref "IC6") (pin "8") (pinfunction "RG_8") (pintype "passive"))
      (node (ref "R31") (pin "1") (pinfunction "1_1") (pintype "passive"))
    )
    (net (code "59") (name "Net-(PWR-PadA)") (class "Default")
      (node (ref "PWR") (pin "A") (pinfunction "A_A") (pintype "passive"))
      (node (ref "R62") (pin "1") (pinfunction "1_1") (pintype "passive"))
    )
    (net (code "60") (name "Net-(R16-Pad2)") (class "Default")
      (node (ref "R16") (pin "2") (pinfunction "2_2") (pintype "passive"))
      (node (ref "R17") (pin "2") (pinfunction "2_2") (pintype "passive"))
      (node (ref "R19") (pin "1") (pinfunction "1_1") (pintype "passive"))
    )
    (net (code "61") (name "Net-(R19-Pad2)") (class "Default")
      (node (ref "R19") (pin "2") (pinfunction "2_2") (pintype "passive"))
      (node (ref "R20") (pin "1") (pinfunction "1_1") (pintype "passive"))
    )
    (net (code "62") (name "Net-(R40-Pad2)") (class "Default")
      (node (ref "R40") (pin "2") (pinfunction "2_2") (pintype "passive"))
      (node (ref "TR1") (pin "1") (pinfunction "1_1") (pintype "passive"))
    )
    (net (code "63") (name "Net-(R41-Pad2)") (class "Default")
      (node (ref "R41") (pin "2") (pinfunction "2_2") (pintype "passive"))
      (node (ref "TR2") (pin "1") (pinfunction "1_1") (pintype "passive"))
    )
    (net (code "64") (name "Net-(SR1-R)") (class "Default")
      (node (ref "R4") (pin "1") (pinfunction "1_1") (pintype "passive"))
      (node (ref "R5") (pin "2") (pinfunction "2_2") (pintype "passive"))
      (node (ref "SR1") (pin "2") (pinfunction "R_2") (pintype "input"))
    )
    (net (code "65") (name "Net-(TCK-PP)") (class "Default")
      (node (ref "TCK") (pin "P$1") (pinfunction "PP_P$1") (pintype "passive"))
      (node (ref "U1") (pin "21") (pinfunction "PC2(TCK)_21") (pintype "bidirectional"))
    )
    (net (code "66") (name "Net-(TDI-PP)") (class "Default")
      (node (ref "TDI") (pin "P$1") (pinfunction "PP_P$1") (pintype "passive"))
      (node (ref "U1") (pin "24") (pinfunction "PC5(TDI)_24") (pintype "bidirectional"))
    )
    (net (code "67") (name "Net-(TDO-PP)") (class "Default")
      (node (ref "TDO") (pin "P$1") (pinfunction "PP_P$1") (pintype "passive"))
      (node (ref "U1") (pin "23") (pinfunction "PC4(TDO)_23") (pintype "bidirectional"))
    )
    (net (code "68") (name "Net-(TMS-PP)") (class "Default")
      (node (ref "TMS") (pin "P$1") (pinfunction "PP_P$1") (pintype "passive"))
      (node (ref "U1") (pin "22") (pinfunction "PC3(TMS)_22") (pintype "bidirectional"))
    )
    (net (code "69") (name "Net-(U1-(ADC2)PA2)") (class "Default")
      (node (ref "C17") (pin "1") (pinfunction "1_1") (pintype "passive"))
      (node (ref "R63") (pin "1") (pinfunction "1_1") (pintype "passive"))
      (node (ref "U1") (pin "35") (pinfunction "(ADC2)PA2_35") (pintype "bidirectional"))
    )
    (net (code "70") (name "Net-(U1-(ADC3)PA3)") (class "Default")
      (node (ref "C16") (pin "1") (pinfunction "1_1") (pintype "passive"))
      (node (ref "R15") (pin "1") (pinfunction "1_1") (pintype "passive"))
      (node (ref "U1") (pin "34") (pinfunction "(ADC3)PA3_34") (pintype "bidirectional"))
    )
    (net (code "71") (name "Net-(U1-(ADC4)PA4)") (class "Default")
      (node (ref "C15") (pin "1") (pinfunction "1_1") (pintype "passive"))
      (node (ref "R14") (pin "1") (pinfunction "1_1") (pintype "passive"))
      (node (ref "U1") (pin "33") (pinfunction "(ADC4)PA4_33") (pintype "bidirectional"))
    )
    (net (code "72") (name "Net-(U1-(ADC5)PA5)") (class "Default")
      (node (ref "C14") (pin "1") (pinfunction "1_1") (pintype "passive"))
      (node (ref "R13") (pin "1") (pinfunction "1_1") (pintype "passive"))
      (node (ref "U1") (pin "32") (pinfunction "(ADC5)PA5_32") (pintype "bidirectional"))
    )
    (net (code "73") (name "Net-(U1-(MISO)PB6)") (class "Default")
      (node (ref "AVR-ISP") (pin "1") (pinfunction "1_1") (pintype "passive"))
      (node (ref "U1") (pin "2") (pinfunction "(MISO)PB6_2") (pintype "bidirectional"))
    )
    (net (code "74") (name "Net-(U1-(MOSI)PB5)") (class "Default")
      (node (ref "AVR-ISP") (pin "4") (pinfunction "4_4") (pintype "passive"))
      (node (ref "U1") (pin "1") (pinfunction "(MOSI)PB5_1") (pintype "bidirectional"))
    )
    (net (code "75") (name "Net-(U1-(RXD)PD0)") (class "Default")
      (node (ref "P/C-CON") (pin "6") (pinfunction "6_6") (pintype "passive"))
      (node (ref "U1") (pin "9") (pinfunction "(RXD)PD0_9") (pintype "bidirectional"))
    )
    (net (code "76") (name "Net-(U1-(SCK)PB7)") (class "Default")
      (node (ref "AVR-ISP") (pin "3") (pinfunction "3_3") (pintype "passive"))
      (node (ref "U1") (pin "3") (pinfunction "(SCK)PB7_3") (pintype "bidirectional"))
    )
    (net (code "77") (name "Net-(U1-(TXD)PD1)") (class "Default")
      (node (ref "P/C-CON") (pin "4") (pinfunction "4_4") (pintype "passive"))
      (node (ref "U1") (pin "10") (pinfunction "(TXD)PD1_10") (pintype "bidirectional"))
    )
    (net (code "78") (name "Net-(U1-AVCC)") (class "Default")
      (node (ref "C4") (pin "1") (pinfunction "1_1") (pintype "passive"))
      (node (ref "R2") (pin "1") (pinfunction "1_1") (pintype "passive"))
      (node (ref "U1") (pin "27") (pinfunction "AVCC_27") (pintype "power_in"))
    )
    (net (code "79") (name "Net-(U1-XTAL1)") (class "Default")
      (node (ref "C3") (pin "1") (pinfunction "1_1") (pintype "passive"))
      (node (ref "Q1") (pin "2") (pinfunction "2_2") (pintype "passive"))
      (node (ref "U1") (pin "8") (pinfunction "XTAL1_8") (pintype "bidirectional"))
    )
    (net (code "80") (name "Net-(U1-XTAL2)") (class "Default")
      (node (ref "C2") (pin "1") (pinfunction "1_1") (pintype "passive"))
      (node (ref "Q1") (pin "1") (pinfunction "1_1") (pintype "passive"))
      (node (ref "U1") (pin "7") (pinfunction "XTAL2_7") (pintype "bidirectional"))
    )
    (net (code "81") (name "Net-(XT-CONA-S)") (class "Default")
      (node (ref "R13") (pin "2") (pinfunction "2_2") (pintype "passive"))
      (node (ref "XT-CON") (pin "1") (pinfunction "S_1") (pintype "passive"))
    )
    (net (code "82") (name "Net-(XT-CONH-S)") (class "Default")
      (node (ref "R14") (pin "2") (pinfunction "2_2") (pintype "passive"))
      (node (ref "XT-CON") (pin "3") (pinfunction "S_3") (pintype "passive"))
    )
    (net (code "83") (name "Net-(XT-CONJ-S)") (class "Default")
      (node (ref "R15") (pin "2") (pinfunction "2_2") (pintype "passive"))
      (node (ref "XT-CON") (pin "5") (pinfunction "S_5") (pintype "passive"))
    )
    (net (code "84") (name "Net-(XT-CONL-S)") (class "Default")
      (node (ref "R63") (pin "2") (pinfunction "2_2") (pintype "passive"))
      (node (ref "XT-CON") (pin "7") (pinfunction "S_7") (pintype "passive"))
    )
    (net (code "85") (name "PE") (class "Default")
      (node (ref "AVR-ISP") (pin "6") (pinfunction "6_6") (pintype "passive"))
      (node (ref "C1") (pin "2") (pinfunction "2_2") (pintype "passive"))
      (node (ref "C2") (pin "2") (pinfunction "2_2") (pintype "passive"))
      (node (ref "C24") (pin "2") (pinfunction "2_2") (pintype "passive"))
      (node (ref "C25") (pin "2") (pinfunction "2_2") (pintype "passive"))
      (node (ref "C26") (pin "-") (pinfunction "-_-") (pintype "passive"))
      (node (ref "C3") (pin "2") (pinfunction "2_2") (pintype "passive"))
      (node (ref "C7") (pin "2") (pinfunction "2_2") (pintype "passive"))
      (node (ref "C72") (pin "2") (pinfunction "2_2") (pintype "passive"))
      (node (ref "C8") (pin "2") (pinfunction "2_2") (pintype "passive"))
      (node (ref "P/C-CON") (pin "3") (pinfunction "3_3") (pintype "passive"))
      (node (ref "P/C-CON") (pin "5") (pinfunction "5_5") (pintype "passive"))
      (node (ref "R52") (pin "2") (pinfunction "2_2") (pintype "passive"))
      (node (ref "U1") (pin "18") (pinfunction "GND1_18") (pintype "bidirectional"))
      (node (ref "U1") (pin "39") (pinfunction "GND2_39") (pintype "bidirectional"))
      (node (ref "U1") (pin "6") (pinfunction "GND_6") (pintype "power_in"))
    )
    (net (code "86") (name "VIN") (class "Default")
      (node (ref "L1") (pin "1") (pinfunction "1_1") (pintype "passive"))
      (node (ref "P/C-CON") (pin "1") (pinfunction "1_1") (pintype "passive"))
      (node (ref "P/C-CON") (pin "2") (pinfunction "2_2") (pintype "passive"))
      (node (ref "R62") (pin "2") (pinfunction "2_2") (pintype "passive"))
    )
    (net (code "87") (name "V_REF") (class "Default")
      (node (ref "C30") (pin "1") (pinfunction "1_1") (pintype "passive"))
      (node (ref "C31") (pin "1") (pinfunction "1_1") (pintype "passive"))
      (node (ref "C32") (pin "+") (pinfunction "+_+") (pintype "passive"))
      (node (ref "C46") (pin "2") (pinfunction "2_2") (pintype "passive"))
      (node (ref "C47") (pin "2") (pinfunction "2_2") (pintype "passive"))
      (node (ref "C49") (pin "2") (pinfunction "2_2") (pintype "passive"))
      (node (ref "C50") (pin "2") (pinfunction "2_2") (pintype "passive"))
      (node (ref "C59") (pin "2") (pinfunction "2_2") (pintype "passive"))
      (node (ref "C60") (pin "2") (pinfunction "2_2") (pintype "passive"))
      (node (ref "C64") (pin "2") (pinfunction "2_2") (pintype "passive"))
      (node (ref "C65") (pin "2") (pinfunction "2_2") (pintype "passive"))
      (node (ref "C67") (pin "2") (pinfunction "2_2") (pintype "passive"))
      (node (ref "C68") (pin "2") (pinfunction "2_2") (pintype "passive"))
      (node (ref "C69") (pin "2") (pinfunction "2_2") (pintype "passive"))
      (node (ref "C71") (pin "2") (pinfunction "2_2") (pintype "passive"))
      (node (ref "CH1_IN+") (pin "4") (pinfunction "4_4") (pintype "bidirectional"))
      (node (ref "CH1_IN-") (pin "4") (pinfunction "4_4") (pintype "bidirectional"))
      (node (ref "CH2_IN+") (pin "4") (pinfunction "4_4") (pintype "bidirectional"))
      (node (ref "CH2_IN-") (pin "4") (pinfunction "4_4") (pintype "bidirectional"))
      (node (ref "DRL-OUT") (pin "2") (pinfunction "2_2") (pintype "passive"))
      (node (ref "IC4") (pin "1") (pinfunction "OUT_1") (pintype "output"))
      (node (ref "IC4") (pin "2") (pinfunction "-IN_2") (pintype "input"))
      (node (ref "IC5") (pin "5") (pinfunction "REF_5") (pintype "passive"))
      (node (ref "IC6") (pin "5") (pinfunction "REF_5") (pintype "passive"))
      (node (ref "R17") (pin "1") (pinfunction "1_1") (pintype "passive"))
      (node (ref "R18") (pin "2") (pinfunction "2_2") (pintype "passive"))
      (node (ref "R36") (pin "2") (pinfunction "2_2") (pintype "passive"))
      (node (ref "R37") (pin "2") (pinfunction "2_2") (pintype "passive"))
      (node (ref "R42") (pin "2") (pinfunction "2_2") (pintype "passive"))
      (node (ref "R43") (pin "2") (pinfunction "2_2") (pintype "passive"))
      (node (ref "R48") (pin "2") (pinfunction "2_2") (pintype "passive"))
      (node (ref "R49") (pin "2") (pinfunction "2_2") (pintype "passive"))
      (node (ref "R53") (pin "1") (pinfunction "1_1") (pintype "passive"))
      (node (ref "R54") (pin "1") (pinfunction "1_1") (pintype "passive"))
      (node (ref "R55") (pin "1") (pinfunction "1_1") (pintype "passive"))
      (node (ref "R8") (pin "1") (pinfunction "1_1") (pintype "passive"))
      (node (ref "TR1") (pin "2") (pinfunction "2_2") (pintype "passive"))
      (node (ref "TR1") (pin "3") (pinfunction "3_3") (pintype "passive"))
      (node (ref "TR2") (pin "2") (pinfunction "2_2") (pintype "passive"))
      (node (ref "TR2") (pin "3") (pinfunction "3_3") (pintype "passive"))
      (node (ref "TR3") (pin "1") (pinfunction "1_1") (pintype "passive"))
      (node (ref "TR3_DIS") (pin "2") (pinfunction "2_2") (pintype "passive"))
      (node (ref "XT-CON") (pin "14") (pinfunction "S_14") (pintype "passive"))
    )
    (net (code "88") (name "unconnected-(DRL-Pad4)") (class "Default")
      (node (ref "DRL") (pin "4") (pinfunction "4_4") (pintype "bidirectional"))
    )
    (net (code "89") (name "unconnected-(U1-(ADC6)PA6-Pad31)") (class "Default")
      (node (ref "U1") (pin "31") (pinfunction "(ADC6)PA6_31") (pintype "bidirectional"))
    )
    (net (code "90") (name "unconnected-(U1-(ADC7)PA7-Pad30)") (class "Default")
      (node (ref "U1") (pin "30") (pinfunction "(ADC7)PA7_30") (pintype "bidirectional"))
    )
    (net (code "91") (name "unconnected-(U1-(AIN0{slash}INT2)PB2-Pad42)") (class "Default")
      (node (ref "U1") (pin "42") (pinfunction "(AIN0/INT2)PB2_42") (pintype "bidirectional"))
    )
    (net (code "92") (name "unconnected-(U1-(AIN1)PB3-Pad43)") (class "Default")
      (node (ref "U1") (pin "43") (pinfunction "(AIN1)PB3_43") (pintype "bidirectional"))
    )
    (net (code "93") (name "unconnected-(U1-(ICP)PD6-Pad15)") (class "Default")
      (node (ref "U1") (pin "15") (pinfunction "(ICP)PD6_15") (pintype "bidirectional"))
    )
    (net (code "94") (name "unconnected-(U1-(INT0)PD2-Pad11)") (class "Default")
      (node (ref "U1") (pin "11") (pinfunction "(INT0)PD2_11") (pintype "bidirectional"))
    )
    (net (code "95") (name "unconnected-(U1-(INT1)PD3-Pad12)") (class "Default")
      (node (ref "U1") (pin "12") (pinfunction "(INT1)PD3_12") (pintype "bidirectional"))
    )
    (net (code "96") (name "unconnected-(U1-(OC1B)PD4-Pad13)") (class "Default")
      (node (ref "U1") (pin "13") (pinfunction "(OC1B)PD4_13") (pintype "bidirectional"))
    )
    (net (code "97") (name "unconnected-(U1-(OC2)PD7-Pad16)") (class "Default")
      (node (ref "U1") (pin "16") (pinfunction "(OC2)PD7_16") (pintype "bidirectional"))
    )
    (net (code "98") (name "unconnected-(U1-(SS)PB4-Pad44)") (class "Default")
      (node (ref "U1") (pin "44") (pinfunction "(SS)PB4_44") (pintype "bidirectional"))
    )
    (net (code "99") (name "unconnected-(U1-(T0)PB0-Pad40)") (class "Default")
      (node (ref "U1") (pin "40") (pinfunction "(T0)PB0_40") (pintype "bidirectional"))
    )
    (net (code "100") (name "unconnected-(U1-(T1)PB1-Pad41)") (class "Default")
      (node (ref "U1") (pin "41") (pinfunction "(T1)PB1_41") (pintype "bidirectional"))
    )
    (net (code "101") (name "unconnected-(U1-(TOSC1)PC6-Pad25)") (class "Default")
      (node (ref "U1") (pin "25") (pinfunction "(TOSC1)PC6_25") (pintype "bidirectional"))
    )
    (net (code "102") (name "unconnected-(U1-(TOSC2)PC7-Pad26)") (class "Default")
      (node (ref "U1") (pin "26") (pinfunction "(TOSC2)PC7_26") (pintype "bidirectional"))
    )
    (net (code "103") (name "unconnected-(U1-PC0(SCL)-Pad19)") (class "Default")
      (node (ref "U1") (pin "19") (pinfunction "PC0(SCL)_19") (pintype "bidirectional"))
    )
    (net (code "104") (name "unconnected-(U1-PC1(SDA)-Pad20)") (class "Default")
      (node (ref "U1") (pin "20") (pinfunction "PC1(SDA)_20") (pintype "bidirectional"))
    )
  )
)
